# Crystal_lamp_Rev6.net
KiCad netlist of a schematic drawn in EAGLE
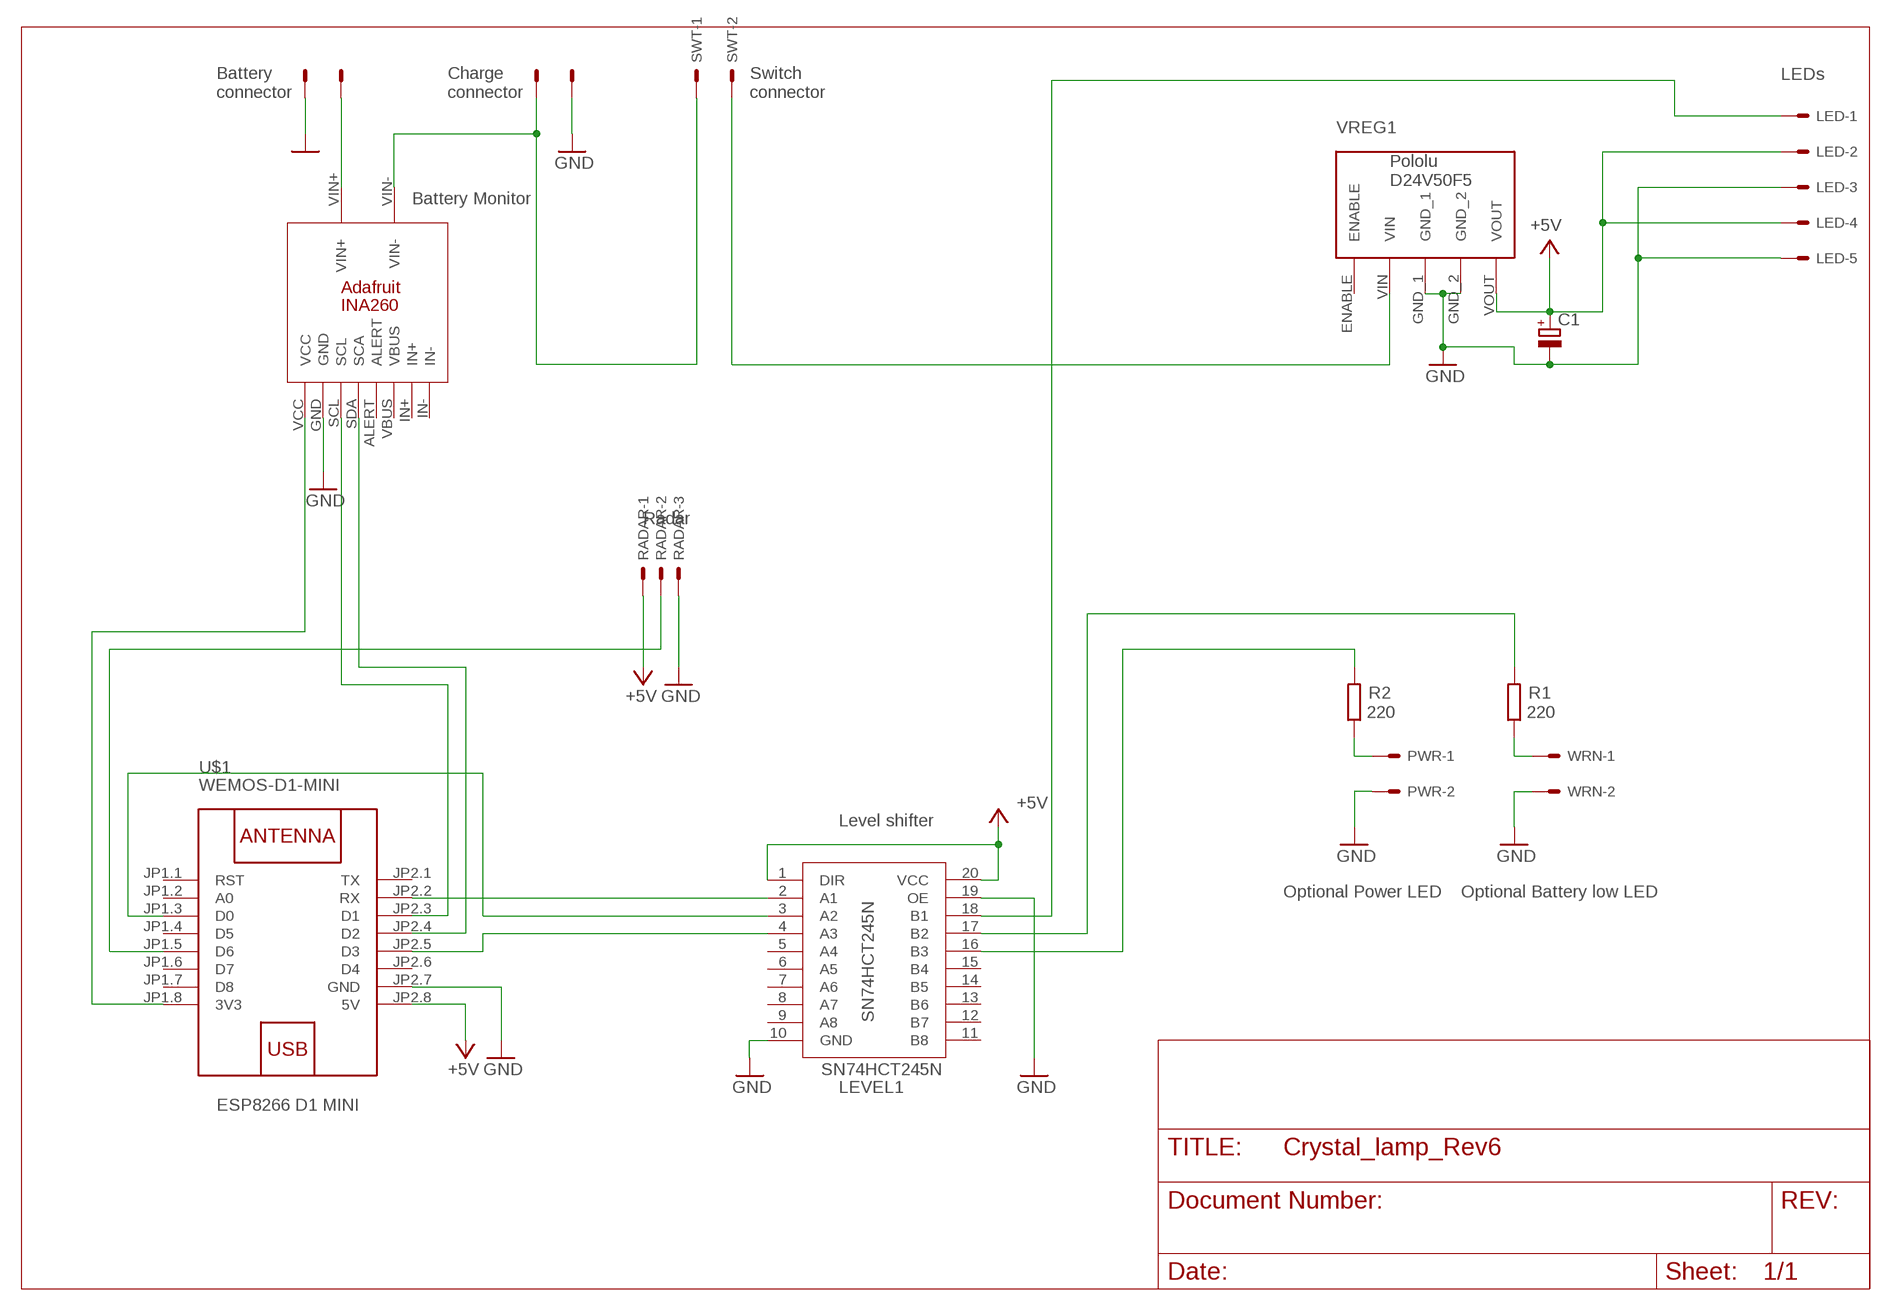
[diagram p0: schematic, sheet 1]

(export (version "E")
  (design (tool "Eeschema 10.0.6"))
  (components
    (comp (ref "BAT")
      (value "22-27-2021-02")
      (footprint "eagle-import:6410-02")
      (fields (field (name "MF") "MOLEX"))
      (libsource (lib "eagle-import") (part "22-?-0227-2021"))
    )
    (comp (ref "C1")
      (value "CPOL-EUE5-10.5")
      (footprint "eagle-import:E5-10,5")
      (libsource (lib "eagle-import") (part "CPOL-EUE5-10.5"))
    )
    (comp (ref "CRG")
      (value "22-27-2021-02")
      (footprint "eagle-import:6410-02")
      (fields (field (name "MF") "MOLEX"))
      (libsource (lib "eagle-import") (part "22-?-0227-2021"))
    )
    (comp (ref "INA1")
      (value "INA260")
      (footprint "eagle-import:INA260")
      (libsource (lib "eagle-import") (part "INA260"))
    )
    (comp (ref "LED")
      (value "22-27-2051-05")
      (footprint "eagle-import:6410-05")
      (fields (field (name "MF") "MOLEX"))
      (libsource (lib "eagle-import") (part "22-?-0527-2051"))
    )
    (comp (ref "LEVEL1")
      (value "SN74HCT245N")
      (footprint "eagle-import:DIL20")
      (libsource (lib "eagle-import") (part "SN74HCT245N"))
    )
    (comp (ref "PWR")
      (value "22-27-2021-02")
      (footprint "eagle-import:6410-02")
      (fields (field (name "MF") "MOLEX"))
      (libsource (lib "eagle-import") (part "22-?-0227-2021"))
    )
    (comp (ref "R1")
      (value "220")
      (footprint "eagle-import:0207_10")
      (libsource (lib "eagle-import") (part "R-EU_0207/10"))
    )
    (comp (ref "R2")
      (value "220")
      (footprint "eagle-import:0207_10")
      (libsource (lib "eagle-import") (part "R-EU_0207/10"))
    )
    (comp (ref "RADAR")
      (value "22-27-2031-03")
      (footprint "eagle-import:6410-03")
      (fields (field (name "MF") "MOLEX"))
      (libsource (lib "eagle-import") (part "22-?-0327-2031"))
    )
    (comp (ref "SWT")
      (value "22-27-2021-02")
      (footprint "eagle-import:6410-02")
      (fields (field (name "MF") "MOLEX"))
      (libsource (lib "eagle-import") (part "22-?-0227-2021"))
    )
    (comp (ref "U$1")
      (value "WEMOS-D1-MINI")
      (footprint "eagle-import:WEMOS-D1-MINI")
      (libsource (lib "eagle-import") (part "WEMOS-D1-MINI"))
    )
    (comp (ref "VREG1")
      (value "D24V50F5")
      (footprint "eagle-import:D24V50F5")
      (libsource (lib "eagle-import") (part "D24V50F5"))
    )
    (comp (ref "WRN")
      (value "22-27-2021-02")
      (footprint "eagle-import:6410-02")
      (fields (field (name "MF") "MOLEX"))
      (libsource (lib "eagle-import") (part "22-?-0227-2021"))
    )
  )
  (nets
    (net (code "1") (name "+5V") (class "Default")
      (node (ref "C1") (pin "+") (pinfunction "+_+") (pintype "passive"))
      (node (ref "LED") (pin "2") (pinfunction "S_2") (pintype "passive"))
      (node (ref "LED") (pin "4") (pinfunction "S_4") (pintype "passive"))
      (node (ref "LEVEL1") (pin "1") (pinfunction "DIR_1") (pintype "bidirectional"))
      (node (ref "LEVEL1") (pin "20") (pinfunction "VCC_20") (pintype "bidirectional"))
      (node (ref "RADAR") (pin "1") (pinfunction "S_1") (pintype "passive"))
      (node (ref "U$1") (pin "JP2.8") (pinfunction "5V_JP2.8") (pintype "power_in"))
      (node (ref "VREG1") (pin "VOUT") (pinfunction "VOUT_VOUT") (pintype "bidirectional"))
    )
    (net (code "2") (name "GND") (class "Default")
      (node (ref "BAT") (pin "2") (pinfunction "S_2") (pintype "passive"))
      (node (ref "C1") (pin "-") (pinfunction "-_-") (pintype "passive"))
      (node (ref "CRG") (pin "2") (pinfunction "S_2") (pintype "passive"))
      (node (ref "INA1") (pin "GND") (pinfunction "GND_GND") (pintype "bidirectional"))
      (node (ref "LED") (pin "3") (pinfunction "S_3") (pintype "passive"))
      (node (ref "LED") (pin "5") (pinfunction "S_5") (pintype "passive"))
      (node (ref "LEVEL1") (pin "10") (pinfunction "GND_10") (pintype "bidirectional"))
      (node (ref "LEVEL1") (pin "19") (pinfunction "OE_19") (pintype "bidirectional"))
      (node (ref "PWR") (pin "2") (pinfunction "S_2") (pintype "passive"))
      (node (ref "RADAR") (pin "3") (pinfunction "S_3") (pintype "passive"))
      (node (ref "U$1") (pin "JP2.7") (pinfunction "GND_JP2.7") (pintype "power_in"))
      (node (ref "VREG1") (pin "GND_1") (pinfunction "GND_1_GND_1") (pintype "bidirectional"))
      (node (ref "VREG1") (pin "GND_2") (pinfunction "GND_2_GND_2") (pintype "bidirectional"))
      (node (ref "WRN") (pin "2") (pinfunction "S_2") (pintype "passive"))
    )
    (net (code "3") (name "Net-(BATA-S)") (class "Default")
      (node (ref "BAT") (pin "1") (pinfunction "S_1") (pintype "passive"))
      (node (ref "INA1") (pin "VIN+") (pinfunction "VIN+_VIN+") (pintype "bidirectional"))
    )
    (net (code "4") (name "Net-(CRGA-S)") (class "Default")
      (node (ref "CRG") (pin "1") (pinfunction "S_1") (pintype "passive"))
      (node (ref "INA1") (pin "VIN-") (pinfunction "VIN-_VIN-") (pintype "bidirectional"))
      (node (ref "SWT") (pin "1") (pinfunction "S_1") (pintype "passive"))
    )
    (net (code "5") (name "Net-(INA1-SCA)") (class "Default")
      (node (ref "INA1") (pin "SDA") (pinfunction "SCA_SDA") (pintype "bidirectional"))
      (node (ref "U$1") (pin "JP2.4") (pinfunction "D2_JP2.4") (pintype "bidirectional"))
    )
    (net (code "6") (name "Net-(LEDA-S)") (class "Default")
      (node (ref "LED") (pin "1") (pinfunction "S_1") (pintype "passive"))
      (node (ref "LEVEL1") (pin "18") (pinfunction "B1_18") (pintype "bidirectional"))
    )
    (net (code "7") (name "Net-(LEVEL1-A1)") (class "Default")
      (node (ref "LEVEL1") (pin "2") (pinfunction "A1_2") (pintype "bidirectional"))
      (node (ref "U$1") (pin "JP2.2") (pinfunction "RX_JP2.2") (pintype "bidirectional"))
    )
    (net (code "8") (name "Net-(LEVEL1-A2)") (class "Default")
      (node (ref "LEVEL1") (pin "3") (pinfunction "A2_3") (pintype "bidirectional"))
      (node (ref "U$1") (pin "JP1.3") (pinfunction "D0_JP1.3") (pintype "bidirectional"))
    )
    (net (code "9") (name "Net-(LEVEL1-A3)") (class "Default")
      (node (ref "LEVEL1") (pin "4") (pinfunction "A3_4") (pintype "bidirectional"))
      (node (ref "U$1") (pin "JP2.5") (pinfunction "D3_JP2.5") (pintype "bidirectional"))
    )
    (net (code "10") (name "Net-(LEVEL1-B2)") (class "Default")
      (node (ref "LEVEL1") (pin "17") (pinfunction "B2_17") (pintype "bidirectional"))
      (node (ref "R1") (pin "2") (pinfunction "2_2") (pintype "passive"))
    )
    (net (code "11") (name "Net-(LEVEL1-B3)") (class "Default")
      (node (ref "LEVEL1") (pin "16") (pinfunction "B3_16") (pintype "bidirectional"))
      (node (ref "R2") (pin "2") (pinfunction "2_2") (pintype "passive"))
    )
    (net (code "12") (name "Net-(PWRA-S)") (class "Default")
      (node (ref "PWR") (pin "1") (pinfunction "S_1") (pintype "passive"))
      (node (ref "R2") (pin "1") (pinfunction "1_1") (pintype "passive"))
    )
    (net (code "13") (name "Net-(RADARB-S)") (class "Default")
      (node (ref "RADAR") (pin "2") (pinfunction "S_2") (pintype "passive"))
      (node (ref "U$1") (pin "JP1.5") (pinfunction "D6_JP1.5") (pintype "bidirectional"))
    )
    (net (code "14") (name "Net-(SWTB-S)") (class "Default")
      (node (ref "SWT") (pin "2") (pinfunction "S_2") (pintype "passive"))
      (node (ref "VREG1") (pin "VIN") (pinfunction "VIN_VIN") (pintype "bidirectional"))
    )
    (net (code "15") (name "Net-(U$1-3V3)") (class "Default")
      (node (ref "INA1") (pin "VCC") (pinfunction "VCC_VCC") (pintype "bidirectional"))
      (node (ref "U$1") (pin "JP1.8") (pinfunction "3V3_JP1.8") (pintype "power_in"))
    )
    (net (code "16") (name "Net-(U$1-D1)") (class "Default")
      (node (ref "INA1") (pin "SCL") (pinfunction "SCL_SCL") (pintype "bidirectional"))
      (node (ref "U$1") (pin "JP2.3") (pinfunction "D1_JP2.3") (pintype "bidirectional"))
    )
    (net (code "17") (name "Net-(WRNA-S)") (class "Default")
      (node (ref "R1") (pin "1") (pinfunction "1_1") (pintype "passive"))
      (node (ref "WRN") (pin "1") (pinfunction "S_1") (pintype "passive"))
    )
    (net (code "18") (name "unconnected-(INA1-PadALERT)") (class "Default")
      (node (ref "INA1") (pin "ALERT") (pinfunction "ALERT_ALERT") (pintype "bidirectional"))
    )
    (net (code "19") (name "unconnected-(INA1-PadIN+)") (class "Default")
      (node (ref "INA1") (pin "IN+") (pinfunction "IN+_IN+") (pintype "bidirectional"))
    )
    (net (code "20") (name "unconnected-(INA1-PadIN-)") (class "Default")
      (node (ref "INA1") (pin "IN-") (pinfunction "IN-_IN-") (pintype "bidirectional"))
    )
    (net (code "21") (name "unconnected-(INA1-PadVBUS)") (class "Default")
      (node (ref "INA1") (pin "VBUS") (pinfunction "VBUS_VBUS") (pintype "bidirectional"))
    )
    (net (code "22") (name "unconnected-(LEVEL1-A4-Pad5)") (class "Default")
      (node (ref "LEVEL1") (pin "5") (pinfunction "A4_5") (pintype "bidirectional"))
    )
    (net (code "23") (name "unconnected-(LEVEL1-A5-Pad6)") (class "Default")
      (node (ref "LEVEL1") (pin "6") (pinfunction "A5_6") (pintype "bidirectional"))
    )
    (net (code "24") (name "unconnected-(LEVEL1-A6-Pad7)") (class "Default")
      (node (ref "LEVEL1") (pin "7") (pinfunction "A6_7") (pintype "bidirectional"))
    )
    (net (code "25") (name "unconnected-(LEVEL1-A7-Pad8)") (class "Default")
      (node (ref "LEVEL1") (pin "8") (pinfunction "A7_8") (pintype "bidirectional"))
    )
    (net (code "26") (name "unconnected-(LEVEL1-A8-Pad9)") (class "Default")
      (node (ref "LEVEL1") (pin "9") (pinfunction "A8_9") (pintype "bidirectional"))
    )
    (net (code "27") (name "unconnected-(LEVEL1-B4-Pad15)") (class "Default")
      (node (ref "LEVEL1") (pin "15") (pinfunction "B4_15") (pintype "bidirectional"))
    )
    (net (code "28") (name "unconnected-(LEVEL1-B5-Pad14)") (class "Default")
      (node (ref "LEVEL1") (pin "14") (pinfunction "B5_14") (pintype "bidirectional"))
    )
    (net (code "29") (name "unconnected-(LEVEL1-B6-Pad13)") (class "Default")
      (node (ref "LEVEL1") (pin "13") (pinfunction "B6_13") (pintype "bidirectional"))
    )
    (net (code "30") (name "unconnected-(LEVEL1-B7-Pad12)") (class "Default")
      (node (ref "LEVEL1") (pin "12") (pinfunction "B7_12") (pintype "bidirectional"))
    )
    (net (code "31") (name "unconnected-(LEVEL1-B8-Pad11)") (class "Default")
      (node (ref "LEVEL1") (pin "11") (pinfunction "B8_11") (pintype "bidirectional"))
    )
    (net (code "32") (name "unconnected-(U$1-A0-PadJP1.2)") (class "Default")
      (node (ref "U$1") (pin "JP1.2") (pinfunction "A0_JP1.2") (pintype "bidirectional"))
    )
    (net (code "33") (name "unconnected-(U$1-D4-PadJP2.6)") (class "Default")
      (node (ref "U$1") (pin "JP2.6") (pinfunction "D4_JP2.6") (pintype "bidirectional"))
    )
    (net (code "34") (name "unconnected-(U$1-D5-PadJP1.4)") (class "Default")
      (node (ref "U$1") (pin "JP1.4") (pinfunction "D5_JP1.4") (pintype "bidirectional"))
    )
    (net (code "35") (name "unconnected-(U$1-D7-PadJP1.6)") (class "Default")
      (node (ref "U$1") (pin "JP1.6") (pinfunction "D7_JP1.6") (pintype "bidirectional"))
    )
    (net (code "36") (name "unconnected-(U$1-D8-PadJP1.7)") (class "Default")
      (node (ref "U$1") (pin "JP1.7") (pinfunction "D8_JP1.7") (pintype "bidirectional"))
    )
    (net (code "37") (name "unconnected-(U$1-RST-PadJP1.1)") (class "Default")
      (node (ref "U$1") (pin "JP1.1") (pinfunction "RST_JP1.1") (pintype "bidirectional"))
    )
    (net (code "38") (name "unconnected-(U$1-TX-PadJP2.1)") (class "Default")
      (node (ref "U$1") (pin "JP2.1") (pinfunction "TX_JP2.1") (pintype "bidirectional"))
    )
    (net (code "39") (name "unconnected-(VREG1-PadENABLE)") (class "Default")
      (node (ref "VREG1") (pin "ENABLE") (pinfunction "ENABLE_ENABLE") (pintype "bidirectional"))
    )
  )
)
